# 6x7.net
KiCad netlist of a schematic drawn in EAGLE
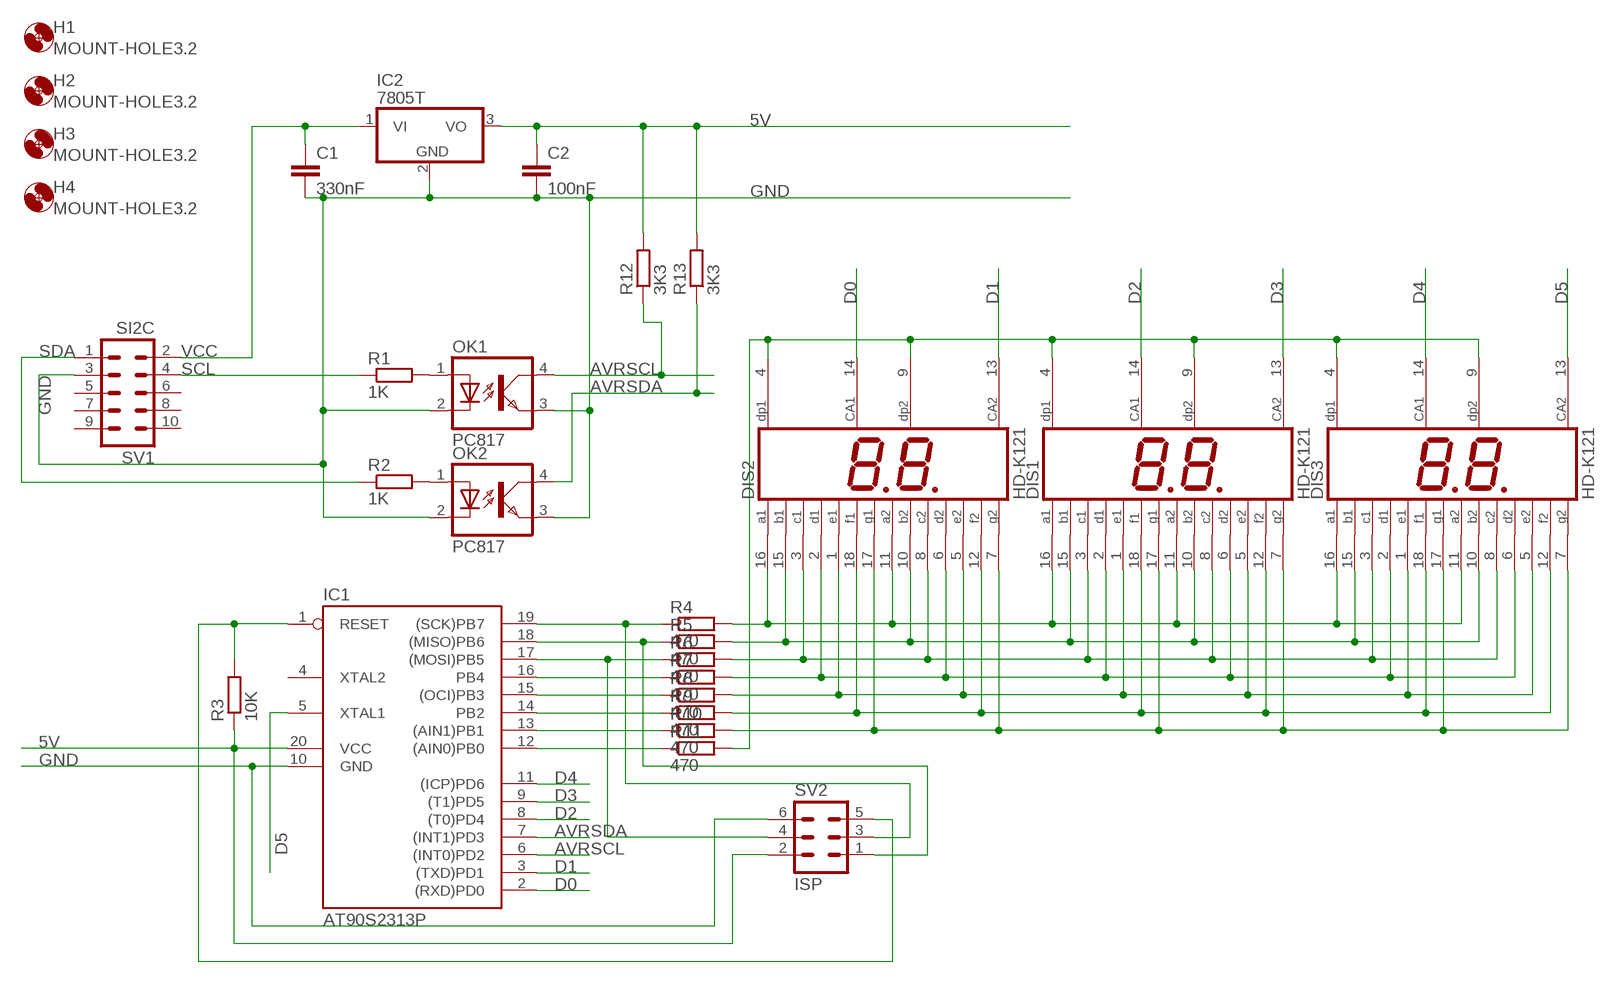
[diagram p0: schematic, sheet 1]

(export (version "E")
  (design (tool "Eeschema 10.0.6"))
  (components
    (comp (ref "C1")
      (value "330nF")
      (footprint "eagle-import:C2.5-3")
      (libsource (lib "eagle-import") (part "C2,5-3"))
    )
    (comp (ref "C2")
      (value "100nF")
      (footprint "eagle-import:C050-024X044")
      (libsource (lib "eagle-import") (part "C-EU050-024X044"))
    )
    (comp (ref "DIS1")
      (value "HD-K121")
      (footprint "eagle-import:HDSP-R")
      (libsource (lib "eagle-import") (part "HD-K121"))
    )
    (comp (ref "DIS2")
      (value "HD-K121")
      (footprint "eagle-import:HDSP-R")
      (libsource (lib "eagle-import") (part "HD-K121"))
    )
    (comp (ref "DIS3")
      (value "HD-K121")
      (footprint "eagle-import:HDSP-R")
      (libsource (lib "eagle-import") (part "HD-K121"))
    )
    (comp (ref "H1")
      (value "MOUNT-HOLE3.2")
      (footprint "eagle-import:3,2")
      (libsource (lib "eagle-import") (part "MOUNT-HOLE3.2"))
    )
    (comp (ref "H2")
      (value "MOUNT-HOLE3.2")
      (footprint "eagle-import:3,2")
      (libsource (lib "eagle-import") (part "MOUNT-HOLE3.2"))
    )
    (comp (ref "H3")
      (value "MOUNT-HOLE3.2")
      (footprint "eagle-import:3,2")
      (libsource (lib "eagle-import") (part "MOUNT-HOLE3.2"))
    )
    (comp (ref "H4")
      (value "MOUNT-HOLE3.2")
      (footprint "eagle-import:3,2")
      (libsource (lib "eagle-import") (part "MOUNT-HOLE3.2"))
    )
    (comp (ref "IC1")
      (value "AT90S2313P")
      (footprint "eagle-import:DIL20")
      (libsource (lib "eagle-import") (part "AT90S2313P"))
    )
    (comp (ref "IC2")
      (value "7805T")
      (footprint "eagle-import:TO220H")
      (libsource (lib "eagle-import") (part "78T05"))
    )
    (comp (ref "OK1")
      (value "PC817")
      (footprint "eagle-import:DIL04")
      (fields (field (name "MPN") "PC817X4J000F"))
      (libsource (lib "eagle-import") (part "PC817"))
    )
    (comp (ref "OK2")
      (value "PC817")
      (footprint "eagle-import:DIL04")
      (fields (field (name "MPN") "PC817X4J000F"))
      (libsource (lib "eagle-import") (part "PC817"))
    )
    (comp (ref "R1")
      (value "1K")
      (footprint "eagle-import:0207_10")
      (libsource (lib "eagle-import") (part "R-EU_0207/10"))
    )
    (comp (ref "R2")
      (value "1K")
      (footprint "eagle-import:0207_10")
      (libsource (lib "eagle-import") (part "R-EU_0207/10"))
    )
    (comp (ref "R3")
      (value "10K")
      (footprint "eagle-import:0207_10")
      (libsource (lib "eagle-import") (part "R-EU_0207/10"))
    )
    (comp (ref "R4")
      (value "470")
      (footprint "eagle-import:0207_10")
      (libsource (lib "eagle-import") (part "R-EU_0207/10"))
    )
    (comp (ref "R5")
      (value "470")
      (footprint "eagle-import:0207_10")
      (libsource (lib "eagle-import") (part "R-EU_0207/10"))
    )
    (comp (ref "R6")
      (value "470")
      (footprint "eagle-import:0207_10")
      (libsource (lib "eagle-import") (part "R-EU_0207/10"))
    )
    (comp (ref "R7")
      (value "470")
      (footprint "eagle-import:0207_10")
      (libsource (lib "eagle-import") (part "R-EU_0207/10"))
    )
    (comp (ref "R8")
      (value "470")
      (footprint "eagle-import:0207_10")
      (libsource (lib "eagle-import") (part "R-EU_0207/10"))
    )
    (comp (ref "R9")
      (value "470")
      (footprint "eagle-import:0207_10")
      (libsource (lib "eagle-import") (part "R-EU_0207/10"))
    )
    (comp (ref "R10")
      (value "470")
      (footprint "eagle-import:0207_10")
      (libsource (lib "eagle-import") (part "R-EU_0207/10"))
    )
    (comp (ref "R11")
      (value "470")
      (footprint "eagle-import:0207_10")
      (libsource (lib "eagle-import") (part "R-EU_0207/10"))
    )
    (comp (ref "R12")
      (value "3K3")
      (footprint "eagle-import:0207_10")
      (libsource (lib "eagle-import") (part "R-EU_0207/10"))
    )
    (comp (ref "R13")
      (value "3K3")
      (footprint "eagle-import:0207_10")
      (libsource (lib "eagle-import") (part "R-EU_0207/10"))
    )
    (comp (ref "SV1")
      (value "SI2C")
      (footprint "eagle-import:ML10")
      (libsource (lib "eagle-import") (part "ML10"))
    )
    (comp (ref "SV2")
      (value "ISP")
      (footprint "eagle-import:ML6")
      (libsource (lib "eagle-import") (part "ML6"))
    )
  )
  (nets
    (net (code "1") (name "/5V") (class "Default")
      (node (ref "C2") (pin "1") (pinfunction "1_1") (pintype "passive"))
      (node (ref "IC1") (pin "20") (pinfunction "VCC_20") (pintype "power_in"))
      (node (ref "IC2") (pin "3") (pinfunction "VO_3") (pintype "passive"))
      (node (ref "R12") (pin "2") (pinfunction "2_2") (pintype "passive"))
      (node (ref "R13") (pin "2") (pinfunction "2_2") (pintype "passive"))
      (node (ref "R3") (pin "1") (pinfunction "1_1") (pintype "passive"))
      (node (ref "SV2") (pin "2") (pinfunction "2_2") (pintype "passive"))
    )
    (net (code "2") (name "/AVRSCL") (class "Default")
      (node (ref "IC1") (pin "6") (pinfunction "(INT0)PD2_6") (pintype "bidirectional"))
      (node (ref "OK1") (pin "4") (pinfunction "COL_4") (pintype "passive"))
      (node (ref "R12") (pin "1") (pinfunction "1_1") (pintype "passive"))
    )
    (net (code "3") (name "/AVRSDA") (class "Default")
      (node (ref "IC1") (pin "7") (pinfunction "(INT1)PD3_7") (pintype "bidirectional"))
      (node (ref "OK2") (pin "4") (pinfunction "COL_4") (pintype "passive"))
      (node (ref "R13") (pin "1") (pinfunction "1_1") (pintype "passive"))
    )
    (net (code "4") (name "/D0") (class "Default")
      (node (ref "DIS2") (pin "14") (pinfunction "CA1_14") (pintype "passive"))
      (node (ref "IC1") (pin "2") (pinfunction "(RXD)PD0_2") (pintype "bidirectional"))
    )
    (net (code "5") (name "/D1") (class "Default")
      (node (ref "DIS2") (pin "13") (pinfunction "CA2_13") (pintype "passive"))
      (node (ref "IC1") (pin "3") (pinfunction "(TXD)PD1_3") (pintype "bidirectional"))
    )
    (net (code "6") (name "/D2") (class "Default")
      (node (ref "DIS1") (pin "14") (pinfunction "CA1_14") (pintype "passive"))
      (node (ref "IC1") (pin "8") (pinfunction "(T0)PD4_8") (pintype "bidirectional"))
    )
    (net (code "7") (name "/D3") (class "Default")
      (node (ref "DIS1") (pin "13") (pinfunction "CA2_13") (pintype "passive"))
      (node (ref "IC1") (pin "9") (pinfunction "(T1)PD5_9") (pintype "bidirectional"))
    )
    (net (code "8") (name "/D4") (class "Default")
      (node (ref "DIS3") (pin "14") (pinfunction "CA1_14") (pintype "passive"))
      (node (ref "IC1") (pin "11") (pinfunction "(ICP)PD6_11") (pintype "bidirectional"))
    )
    (net (code "9") (name "/D5") (class "Default")
      (node (ref "DIS3") (pin "13") (pinfunction "CA2_13") (pintype "passive"))
      (node (ref "IC1") (pin "5") (pinfunction "XTAL1_5") (pintype "bidirectional"))
    )
    (net (code "10") (name "/GND") (class "Default")
      (node (ref "C1") (pin "2") (pinfunction "2_2") (pintype "passive"))
      (node (ref "C2") (pin "2") (pinfunction "2_2") (pintype "passive"))
      (node (ref "IC1") (pin "10") (pinfunction "GND_10") (pintype "power_in"))
      (node (ref "IC2") (pin "2") (pinfunction "GND_2") (pintype "passive"))
      (node (ref "OK1") (pin "2") (pinfunction "C_2") (pintype "passive"))
      (node (ref "OK1") (pin "3") (pinfunction "EMIT_3") (pintype "passive"))
      (node (ref "OK2") (pin "2") (pinfunction "C_2") (pintype "passive"))
      (node (ref "OK2") (pin "3") (pinfunction "EMIT_3") (pintype "passive"))
      (node (ref "SV1") (pin "3") (pinfunction "3_3") (pintype "passive"))
      (node (ref "SV2") (pin "6") (pinfunction "6_6") (pintype "passive"))
    )
    (net (code "11") (name "/SCL") (class "Default")
      (node (ref "R1") (pin "1") (pinfunction "1_1") (pintype "passive"))
      (node (ref "SV1") (pin "4") (pinfunction "4_4") (pintype "passive"))
    )
    (net (code "12") (name "/SDA") (class "Default")
      (node (ref "R2") (pin "1") (pinfunction "1_1") (pintype "passive"))
      (node (ref "SV1") (pin "1") (pinfunction "1_1") (pintype "passive"))
    )
    (net (code "13") (name "/VCC") (class "Default")
      (node (ref "C1") (pin "1") (pinfunction "1_1") (pintype "passive"))
      (node (ref "IC2") (pin "1") (pinfunction "VI_1") (pintype "input"))
      (node (ref "SV1") (pin "2") (pinfunction "2_2") (pintype "passive"))
    )
    (net (code "14") (name "Net-(DIS1-A1)") (class "Default")
      (node (ref "DIS1") (pin "11") (pinfunction "A2_11") (pintype "passive"))
      (node (ref "DIS1") (pin "16") (pinfunction "A1_16") (pintype "passive"))
      (node (ref "DIS2") (pin "11") (pinfunction "A2_11") (pintype "passive"))
      (node (ref "DIS2") (pin "16") (pinfunction "A1_16") (pintype "passive"))
      (node (ref "DIS3") (pin "11") (pinfunction "A2_11") (pintype "passive"))
      (node (ref "DIS3") (pin "16") (pinfunction "A1_16") (pintype "passive"))
      (node (ref "R4") (pin "2") (pinfunction "2_2") (pintype "passive"))
    )
    (net (code "15") (name "Net-(DIS1-B1)") (class "Default")
      (node (ref "DIS1") (pin "10") (pinfunction "B2_10") (pintype "passive"))
      (node (ref "DIS1") (pin "15") (pinfunction "B1_15") (pintype "passive"))
      (node (ref "DIS2") (pin "10") (pinfunction "B2_10") (pintype "passive"))
      (node (ref "DIS2") (pin "15") (pinfunction "B1_15") (pintype "passive"))
      (node (ref "DIS3") (pin "10") (pinfunction "B2_10") (pintype "passive"))
      (node (ref "DIS3") (pin "15") (pinfunction "B1_15") (pintype "passive"))
      (node (ref "R5") (pin "2") (pinfunction "2_2") (pintype "passive"))
    )
    (net (code "16") (name "Net-(DIS1-C1)") (class "Default")
      (node (ref "DIS1") (pin "3") (pinfunction "C1_3") (pintype "passive"))
      (node (ref "DIS1") (pin "8") (pinfunction "C2_8") (pintype "passive"))
      (node (ref "DIS2") (pin "3") (pinfunction "C1_3") (pintype "passive"))
      (node (ref "DIS2") (pin "8") (pinfunction "C2_8") (pintype "passive"))
      (node (ref "DIS3") (pin "3") (pinfunction "C1_3") (pintype "passive"))
      (node (ref "DIS3") (pin "8") (pinfunction "C2_8") (pintype "passive"))
      (node (ref "R6") (pin "2") (pinfunction "2_2") (pintype "passive"))
    )
    (net (code "17") (name "Net-(DIS1-D1)") (class "Default")
      (node (ref "DIS1") (pin "2") (pinfunction "D1_2") (pintype "passive"))
      (node (ref "DIS1") (pin "6") (pinfunction "D2_6") (pintype "passive"))
      (node (ref "DIS2") (pin "2") (pinfunction "D1_2") (pintype "passive"))
      (node (ref "DIS2") (pin "6") (pinfunction "D2_6") (pintype "passive"))
      (node (ref "DIS3") (pin "2") (pinfunction "D1_2") (pintype "passive"))
      (node (ref "DIS3") (pin "6") (pinfunction "D2_6") (pintype "passive"))
      (node (ref "R7") (pin "2") (pinfunction "2_2") (pintype "passive"))
    )
    (net (code "18") (name "Net-(DIS1-DP1)") (class "Default")
      (node (ref "DIS1") (pin "4") (pinfunction "DP1_4") (pintype "passive"))
      (node (ref "DIS1") (pin "9") (pinfunction "DP2_9") (pintype "passive"))
      (node (ref "DIS2") (pin "4") (pinfunction "DP1_4") (pintype "passive"))
      (node (ref "DIS2") (pin "9") (pinfunction "DP2_9") (pintype "passive"))
      (node (ref "DIS3") (pin "4") (pinfunction "DP1_4") (pintype "passive"))
      (node (ref "DIS3") (pin "9") (pinfunction "DP2_9") (pintype "passive"))
      (node (ref "R11") (pin "2") (pinfunction "2_2") (pintype "passive"))
    )
    (net (code "19") (name "Net-(DIS1-E1)") (class "Default")
      (node (ref "DIS1") (pin "1") (pinfunction "E1_1") (pintype "passive"))
      (node (ref "DIS1") (pin "5") (pinfunction "E2_5") (pintype "passive"))
      (node (ref "DIS2") (pin "1") (pinfunction "E1_1") (pintype "passive"))
      (node (ref "DIS2") (pin "5") (pinfunction "E2_5") (pintype "passive"))
      (node (ref "DIS3") (pin "1") (pinfunction "E1_1") (pintype "passive"))
      (node (ref "DIS3") (pin "5") (pinfunction "E2_5") (pintype "passive"))
      (node (ref "R8") (pin "2") (pinfunction "2_2") (pintype "passive"))
    )
    (net (code "20") (name "Net-(DIS1-F1)") (class "Default")
      (node (ref "DIS1") (pin "12") (pinfunction "F2_12") (pintype "passive"))
      (node (ref "DIS1") (pin "18") (pinfunction "F1_18") (pintype "passive"))
      (node (ref "DIS2") (pin "12") (pinfunction "F2_12") (pintype "passive"))
      (node (ref "DIS2") (pin "18") (pinfunction "F1_18") (pintype "passive"))
      (node (ref "DIS3") (pin "12") (pinfunction "F2_12") (pintype "passive"))
      (node (ref "DIS3") (pin "18") (pinfunction "F1_18") (pintype "passive"))
      (node (ref "R9") (pin "2") (pinfunction "2_2") (pintype "passive"))
    )
    (net (code "21") (name "Net-(DIS1-G1)") (class "Default")
      (node (ref "DIS1") (pin "17") (pinfunction "G1_17") (pintype "passive"))
      (node (ref "DIS1") (pin "7") (pinfunction "G2_7") (pintype "passive"))
      (node (ref "DIS2") (pin "17") (pinfunction "G1_17") (pintype "passive"))
      (node (ref "DIS2") (pin "7") (pinfunction "G2_7") (pintype "passive"))
      (node (ref "DIS3") (pin "17") (pinfunction "G1_17") (pintype "passive"))
      (node (ref "DIS3") (pin "7") (pinfunction "G2_7") (pintype "passive"))
      (node (ref "R10") (pin "2") (pinfunction "2_2") (pintype "passive"))
    )
    (net (code "22") (name "Net-(IC1-(AIN0)PB0)") (class "Default")
      (node (ref "IC1") (pin "12") (pinfunction "(AIN0)PB0_12") (pintype "bidirectional"))
      (node (ref "R11") (pin "1") (pinfunction "1_1") (pintype "passive"))
    )
    (net (code "23") (name "Net-(IC1-(AIN1)PB1)") (class "Default")
      (node (ref "IC1") (pin "13") (pinfunction "(AIN1)PB1_13") (pintype "bidirectional"))
      (node (ref "R10") (pin "1") (pinfunction "1_1") (pintype "passive"))
    )
    (net (code "24") (name "Net-(IC1-(MISO)PB6)") (class "Default")
      (node (ref "IC1") (pin "18") (pinfunction "(MISO)PB6_18") (pintype "bidirectional"))
      (node (ref "R5") (pin "1") (pinfunction "1_1") (pintype "passive"))
      (node (ref "SV2") (pin "1") (pinfunction "1_1") (pintype "passive"))
    )
    (net (code "25") (name "Net-(IC1-(MOSI)PB5)") (class "Default")
      (node (ref "IC1") (pin "17") (pinfunction "(MOSI)PB5_17") (pintype "bidirectional"))
      (node (ref "R6") (pin "1") (pinfunction "1_1") (pintype "passive"))
      (node (ref "SV2") (pin "4") (pinfunction "4_4") (pintype "passive"))
    )
    (net (code "26") (name "Net-(IC1-(OCI)PB3)") (class "Default")
      (node (ref "IC1") (pin "15") (pinfunction "(OCI)PB3_15") (pintype "bidirectional"))
      (node (ref "R8") (pin "1") (pinfunction "1_1") (pintype "passive"))
    )
    (net (code "27") (name "Net-(IC1-(SCK)PB7)") (class "Default")
      (node (ref "IC1") (pin "19") (pinfunction "(SCK)PB7_19") (pintype "bidirectional"))
      (node (ref "R4") (pin "1") (pinfunction "1_1") (pintype "passive"))
      (node (ref "SV2") (pin "3") (pinfunction "3_3") (pintype "passive"))
    )
    (net (code "28") (name "Net-(IC1-PB2)") (class "Default")
      (node (ref "IC1") (pin "14") (pinfunction "PB2_14") (pintype "bidirectional"))
      (node (ref "R9") (pin "1") (pinfunction "1_1") (pintype "passive"))
    )
    (net (code "29") (name "Net-(IC1-PB4)") (class "Default")
      (node (ref "IC1") (pin "16") (pinfunction "PB4_16") (pintype "bidirectional"))
      (node (ref "R7") (pin "1") (pinfunction "1_1") (pintype "passive"))
    )
    (net (code "30") (name "Net-(IC1-RESET)") (class "Default")
      (node (ref "IC1") (pin "1") (pinfunction "RESET_1") (pintype "bidirectional"))
      (node (ref "R3") (pin "2") (pinfunction "2_2") (pintype "passive"))
      (node (ref "SV2") (pin "5") (pinfunction "5_5") (pintype "passive"))
    )
    (net (code "31") (name "Net-(OK1-A)") (class "Default")
      (node (ref "OK1") (pin "1") (pinfunction "A_1") (pintype "passive"))
      (node (ref "R1") (pin "2") (pinfunction "2_2") (pintype "passive"))
    )
    (net (code "32") (name "Net-(OK2-A)") (class "Default")
      (node (ref "OK2") (pin "1") (pinfunction "A_1") (pintype "passive"))
      (node (ref "R2") (pin "2") (pinfunction "2_2") (pintype "passive"))
    )
    (net (code "33") (name "unconnected-(IC1-XTAL2-Pad4)") (class "Default")
      (node (ref "IC1") (pin "4") (pinfunction "XTAL2_4") (pintype "bidirectional"))
    )
    (net (code "34") (name "unconnected-(SV1-Pad5)") (class "Default")
      (node (ref "SV1") (pin "5") (pinfunction "5_5") (pintype "passive"))
    )
    (net (code "35") (name "unconnected-(SV1-Pad6)") (class "Default")
      (node (ref "SV1") (pin "6") (pinfunction "6_6") (pintype "passive"))
    )
    (net (code "36") (name "unconnected-(SV1-Pad7)") (class "Default")
      (node (ref "SV1") (pin "7") (pinfunction "7_7") (pintype "passive"))
    )
    (net (code "37") (name "unconnected-(SV1-Pad8)") (class "Default")
      (node (ref "SV1") (pin "8") (pinfunction "8_8") (pintype "passive"))
    )
    (net (code "38") (name "unconnected-(SV1-Pad9)") (class "Default")
      (node (ref "SV1") (pin "9") (pinfunction "9_9") (pintype "passive"))
    )
    (net (code "39") (name "unconnected-(SV1-Pad10)") (class "Default")
      (node (ref "SV1") (pin "10") (pinfunction "10_10") (pintype "passive"))
    )
  )
)
